# Buzzer.net
KiCad netlist of a schematic drawn in Altium Designer
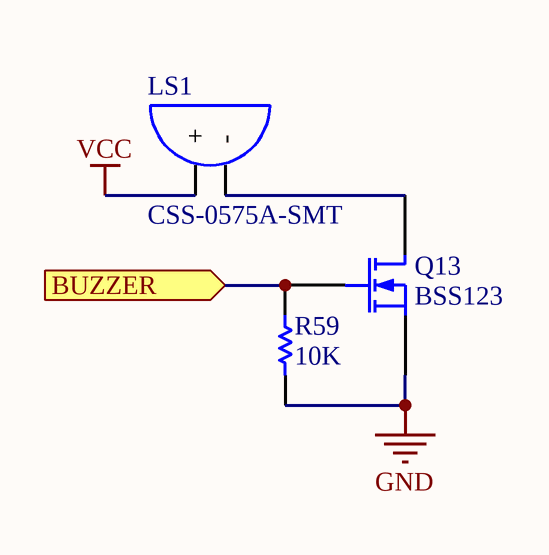
[diagram p0: Buzzer.SchDoc]

(export (version "E")
  (design (tool "Eeschema 10.0.6"))
  (components
    (comp (ref "LS1")
      (value "CSS-0575A-SMT")
      (footprint "CSS-0575A-SMT")
      (description "Magnetic Buzzer Transducer")
      (fields (field (name "MANUFACTURER") "CUI, Inc."))
      (libsource (lib "Components") (part "CSS-0575A-SMT"))
    )
    (comp (ref "Q13")
      (value "BSS123")
      (footprint "SOT323-3")
      (description "N-Channel MOSFET")
      (fields (field (name "PARTNUMBER") "BSS123WQ-7-F") (field (name "MANUFACTURER") "Diodes Incorporated"))
      (libsource (lib "MOSFETs") (part "BSS123WQ-7-F"))
    )
    (comp (ref "R59")
      (value "10K")
      (footprint "R0402[1005]")
      (description "10K 0.063W 1% 0402 (1005 Metric)")
      (fields (field (name "MANUFACTURER") "KOA Speer") (field (name "PARTNUMBER") "RK73H1ETTP1002F"))
      (libsource (lib "Resistors") (part "RES_10K_0402_1%"))
    )
  )
  (nets
    (net (code "1") (name "/BUZZER") (class "Default")
      (node (ref "Q13") (pin "1") (pinfunction "G_1") (pintype "passive"))
      (node (ref "R59") (pin "2") (pinfunction "2_2") (pintype "passive"))
    )
    (net (code "2") (name "GND") (class "Default")
      (node (ref "Q13") (pin "2") (pinfunction "S_2") (pintype "passive"))
      (node (ref "R59") (pin "1") (pinfunction "1_1") (pintype "passive"))
    )
    (net (code "3") (name "Net-(LS1--)") (class "Default")
      (node (ref "LS1") (pin "2") (pinfunction "-_2") (pintype "passive"))
      (node (ref "Q13") (pin "3") (pinfunction "D_3") (pintype "passive"))
    )
    (net (code "4") (name "VCC") (class "Default")
      (node (ref "LS1") (pin "1") (pinfunction "+_1") (pintype "passive"))
    )
  )
)
